# makeToneBoard.net
KiCad netlist of a schematic drawn in EAGLE
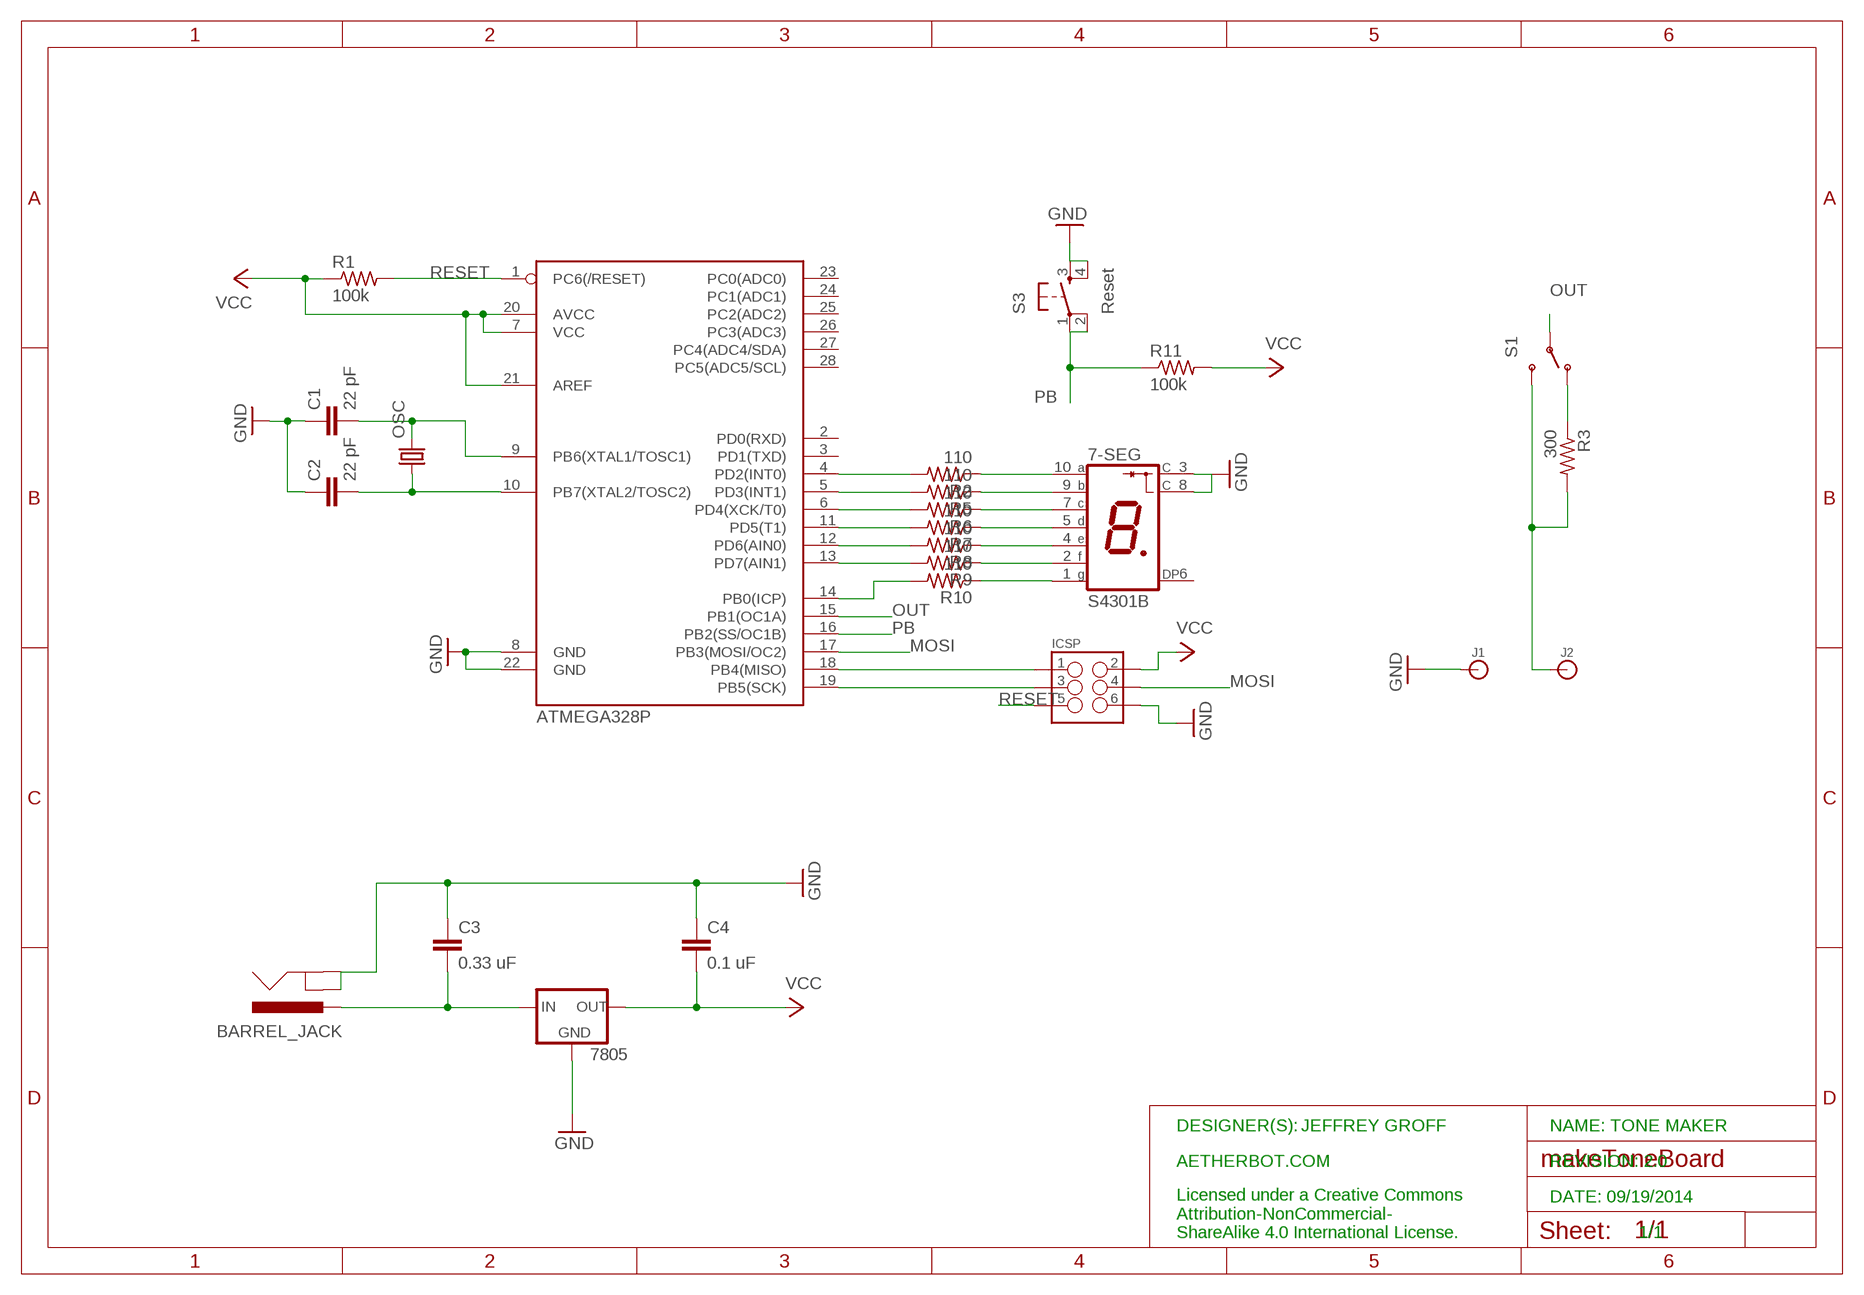
[diagram p0: schematic, sheet 1]

(export (version "E")
  (design (tool "Eeschema 10.0.6"))
  (components
    (comp (ref "7-SEG")
      (value "S4301B")
      (footprint "eagle-import:S4301B")
      (libsource (lib "eagle-import") (part "S4301B"))
    )
    (comp (ref "7805")
      (value "V_REG_78XXSINK")
      (footprint "eagle-import:TO220-IGO")
      (libsource (lib "eagle-import") (part "V_REG_78XXSINK"))
    )
    (comp (ref "BARREL_JACK")
      (value "POWER_JACKPTH")
      (footprint "eagle-import:POWER_JACK_PTH")
      (libsource (lib "eagle-import") (part "POWER_JACKPTH"))
    )
    (comp (ref "C1")
      (value "22 pF")
      (footprint "eagle-import:CAP-PTH-SMALL-KIT")
      (libsource (lib "eagle-import") (part "CAPKIT"))
    )
    (comp (ref "C2")
      (value "22 pF")
      (footprint "eagle-import:CAP-PTH-SMALL-KIT")
      (libsource (lib "eagle-import") (part "CAPKIT"))
    )
    (comp (ref "C3")
      (value "0.33 uF")
      (footprint "eagle-import:CAP-PTH-SMALLEZ")
      (libsource (lib "eagle-import") (part "CAPEZ"))
    )
    (comp (ref "C4")
      (value "0.1 uF")
      (footprint "eagle-import:CAP-PTH-SMALLEZ")
      (libsource (lib "eagle-import") (part "CAPEZ"))
    )
    (comp (ref "ICSP")
      (value "M03X2NO_SILK")
      (footprint "eagle-import:2X3-NS")
      (libsource (lib "eagle-import") (part "M03X2NO_SILK"))
    )
    (comp (ref "J1")
      (value "BANANA_CONN")
      (footprint "eagle-import:BANANA_CONN")
      (libsource (lib "eagle-import") (part "BANANA_CONN"))
    )
    (comp (ref "J2")
      (value "BANANA_CONN")
      (footprint "eagle-import:BANANA_CONN")
      (libsource (lib "eagle-import") (part "BANANA_CONN"))
    )
    (comp (ref "OSC")
      (value "CRYSTALHC49S")
      (footprint "eagle-import:HC49_S")
      (libsource (lib "eagle-import") (part "CRYSTALHC49S"))
    )
    (comp (ref "R1")
      (value "100k")
      (footprint "eagle-import:0204_7")
      (libsource (lib "eagle-import") (part "R-US_0204/7"))
    )
    (comp (ref "R2")
      (value "110")
      (footprint "eagle-import:0204_7")
      (libsource (lib "eagle-import") (part "R-US_0204/7"))
    )
    (comp (ref "R3")
      (value "300")
      (footprint "eagle-import:0204_7")
      (libsource (lib "eagle-import") (part "R-US_0204/7"))
    )
    (comp (ref "R5")
      (value "110")
      (footprint "eagle-import:0204_7")
      (libsource (lib "eagle-import") (part "R-US_0204/7"))
    )
    (comp (ref "R6")
      (value "110")
      (footprint "eagle-import:0204_7")
      (libsource (lib "eagle-import") (part "R-US_0204/7"))
    )
    (comp (ref "R7")
      (value "110")
      (footprint "eagle-import:0204_7")
      (libsource (lib "eagle-import") (part "R-US_0204/7"))
    )
    (comp (ref "R8")
      (value "110")
      (footprint "eagle-import:0204_7")
      (libsource (lib "eagle-import") (part "R-US_0204/7"))
    )
    (comp (ref "R9")
      (value "110")
      (footprint "eagle-import:0204_7")
      (libsource (lib "eagle-import") (part "R-US_0204/7"))
    )
    (comp (ref "R10")
      (value "110")
      (footprint "eagle-import:0204_7")
      (libsource (lib "eagle-import") (part "R-US_0204/7"))
    )
    (comp (ref "R11")
      (value "100k")
      (footprint "eagle-import:0204_7")
      (libsource (lib "eagle-import") (part "R-US_0204/7"))
    )
    (comp (ref "S1")
      (value "LED PWR")
      (footprint "eagle-import:SWITCH-SPDT")
      (libsource (lib "eagle-import") (part "SWITCH-SPDTPTH"))
    )
    (comp (ref "S3")
      (value "Reset")
      (footprint "eagle-import:TACTILE-PTH")
      (libsource (lib "eagle-import") (part "TAC_SWITCHPTH"))
    )
    (comp (ref "U1")
      (value "ATMEGA328P")
      (footprint "eagle-import:DIL28-3")
      (libsource (lib "eagle-import") (part "ATMEGA328P_PDIP"))
    )
  )
  (nets
    (net (code "1") (name "/MOSI") (class "Default")
      (node (ref "ICSP") (pin "4") (pinfunction "4_4") (pintype "bidirectional"))
      (node (ref "U1") (pin "17") (pinfunction "PB3(MOSI/OC2)_17") (pintype "bidirectional"))
    )
    (net (code "2") (name "/OUT") (class "Default")
      (node (ref "S1") (pin "2") (pinfunction "P_2") (pintype "passive"))
      (node (ref "U1") (pin "15") (pinfunction "PB1(OC1A)_15") (pintype "bidirectional"))
    )
    (net (code "3") (name "/PB") (class "Default")
      (node (ref "R11") (pin "1") (pinfunction "1_1") (pintype "passive"))
      (node (ref "S3") (pin "1") (pinfunction "1_1") (pintype "passive"))
      (node (ref "S3") (pin "2") (pinfunction "2_2") (pintype "passive"))
      (node (ref "U1") (pin "16") (pinfunction "PB2(SS/OC1B)_16") (pintype "bidirectional"))
    )
    (net (code "4") (name "/RESET") (class "Default")
      (node (ref "ICSP") (pin "5") (pinfunction "5_5") (pintype "bidirectional"))
      (node (ref "R1") (pin "2") (pinfunction "2_2") (pintype "passive"))
      (node (ref "U1") (pin "1") (pinfunction "PC6(/RESET)_1") (pintype "bidirectional"))
    )
    (net (code "5") (name "GND") (class "Default")
      (node (ref "7-SEG") (pin "3") (pinfunction "C_3") (pintype "passive"))
      (node (ref "7-SEG") (pin "8") (pinfunction "C_8") (pintype "passive"))
      (node (ref "7805") (pin "GND") (pinfunction "GND_GND") (pintype "input"))
      (node (ref "BARREL_JACK") (pin "GND") (pinfunction "GND_GND") (pintype "bidirectional"))
      (node (ref "BARREL_JACK") (pin "GNDBREAK") (pinfunction "GNDBREAK_GNDBREAK") (pintype "bidirectional"))
      (node (ref "C1") (pin "1") (pinfunction "1_1") (pintype "passive"))
      (node (ref "C2") (pin "1") (pinfunction "1_1") (pintype "passive"))
      (node (ref "C3") (pin "1") (pinfunction "1_1") (pintype "passive"))
      (node (ref "C4") (pin "1") (pinfunction "1_1") (pintype "passive"))
      (node (ref "ICSP") (pin "6") (pinfunction "6_6") (pintype "bidirectional"))
      (node (ref "J1") (pin "P$1") (pinfunction "1_P$1") (pintype "passive"))
      (node (ref "S3") (pin "3") (pinfunction "3_3") (pintype "passive"))
      (node (ref "S3") (pin "4") (pinfunction "4_4") (pintype "passive"))
      (node (ref "U1") (pin "22") (pinfunction "GND_22") (pintype "bidirectional"))
      (node (ref "U1") (pin "8") (pinfunction "GND_8") (pintype "bidirectional"))
    )
    (net (code "6") (name "Net-(7-SEG-A)") (class "Default")
      (node (ref "7-SEG") (pin "10") (pinfunction "A_10") (pintype "passive"))
      (node (ref "R2") (pin "1") (pinfunction "1_1") (pintype "passive"))
    )
    (net (code "7") (name "Net-(7-SEG-B)") (class "Default")
      (node (ref "7-SEG") (pin "9") (pinfunction "B_9") (pintype "passive"))
      (node (ref "R5") (pin "1") (pinfunction "1_1") (pintype "passive"))
    )
    (net (code "8") (name "Net-(7-SEG-C-Pad7)") (class "Default")
      (node (ref "7-SEG") (pin "7") (pinfunction "C_7") (pintype "passive"))
      (node (ref "R6") (pin "1") (pinfunction "1_1") (pintype "passive"))
    )
    (net (code "9") (name "Net-(7-SEG-D)") (class "Default")
      (node (ref "7-SEG") (pin "5") (pinfunction "D_5") (pintype "passive"))
      (node (ref "R7") (pin "1") (pinfunction "1_1") (pintype "passive"))
    )
    (net (code "10") (name "Net-(7-SEG-E)") (class "Default")
      (node (ref "7-SEG") (pin "4") (pinfunction "E_4") (pintype "passive"))
      (node (ref "R8") (pin "1") (pinfunction "1_1") (pintype "passive"))
    )
    (net (code "11") (name "Net-(7-SEG-F)") (class "Default")
      (node (ref "7-SEG") (pin "2") (pinfunction "F_2") (pintype "passive"))
      (node (ref "R9") (pin "1") (pinfunction "1_1") (pintype "passive"))
    )
    (net (code "12") (name "Net-(7-SEG-G)") (class "Default")
      (node (ref "7-SEG") (pin "1") (pinfunction "G_1") (pintype "passive"))
      (node (ref "R10") (pin "1") (pinfunction "1_1") (pintype "passive"))
    )
    (net (code "13") (name "Net-(7805-PadIN)") (class "Default")
      (node (ref "7805") (pin "IN") (pinfunction "IN_IN") (pintype "input"))
      (node (ref "BARREL_JACK") (pin "PWR") (pinfunction "PWR_PWR") (pintype "bidirectional"))
      (node (ref "C3") (pin "2") (pinfunction "2_2") (pintype "passive"))
    )
    (net (code "14") (name "Net-(J2-1)") (class "Default")
      (node (ref "J2") (pin "P$1") (pinfunction "1_P$1") (pintype "passive"))
      (node (ref "R3") (pin "2") (pinfunction "2_2") (pintype "passive"))
      (node (ref "S1") (pin "3") (pinfunction "S_3") (pintype "passive"))
    )
    (net (code "15") (name "Net-(S1-O)") (class "Default")
      (node (ref "R3") (pin "1") (pinfunction "1_1") (pintype "passive"))
      (node (ref "S1") (pin "1") (pinfunction "O_1") (pintype "passive"))
    )
    (net (code "16") (name "Net-(U1-PB0(ICP))") (class "Default")
      (node (ref "R10") (pin "2") (pinfunction "2_2") (pintype "passive"))
      (node (ref "U1") (pin "14") (pinfunction "PB0(ICP)_14") (pintype "bidirectional"))
    )
    (net (code "17") (name "Net-(U1-PB4(MISO))") (class "Default")
      (node (ref "ICSP") (pin "1") (pinfunction "1_1") (pintype "bidirectional"))
      (node (ref "U1") (pin "18") (pinfunction "PB4(MISO)_18") (pintype "bidirectional"))
    )
    (net (code "18") (name "Net-(U1-PB5(SCK))") (class "Default")
      (node (ref "ICSP") (pin "3") (pinfunction "3_3") (pintype "bidirectional"))
      (node (ref "U1") (pin "19") (pinfunction "PB5(SCK)_19") (pintype "bidirectional"))
    )
    (net (code "19") (name "Net-(U1-PB6(XTAL1{slash}TOSC1))") (class "Default")
      (node (ref "C1") (pin "2") (pinfunction "2_2") (pintype "passive"))
      (node (ref "OSC") (pin "2") (pinfunction "2_2") (pintype "passive"))
      (node (ref "U1") (pin "9") (pinfunction "PB6(XTAL1/TOSC1)_9") (pintype "bidirectional"))
    )
    (net (code "20") (name "Net-(U1-PB7(XTAL2{slash}TOSC2))") (class "Default")
      (node (ref "C2") (pin "2") (pinfunction "2_2") (pintype "passive"))
      (node (ref "OSC") (pin "1") (pinfunction "1_1") (pintype "passive"))
      (node (ref "U1") (pin "10") (pinfunction "PB7(XTAL2/TOSC2)_10") (pintype "bidirectional"))
    )
    (net (code "21") (name "Net-(U1-PD2(INT0))") (class "Default")
      (node (ref "R2") (pin "2") (pinfunction "2_2") (pintype "passive"))
      (node (ref "U1") (pin "4") (pinfunction "PD2(INT0)_4") (pintype "bidirectional"))
    )
    (net (code "22") (name "Net-(U1-PD3(INT1))") (class "Default")
      (node (ref "R5") (pin "2") (pinfunction "2_2") (pintype "passive"))
      (node (ref "U1") (pin "5") (pinfunction "PD3(INT1)_5") (pintype "bidirectional"))
    )
    (net (code "23") (name "Net-(U1-PD4(XCK{slash}T0))") (class "Default")
      (node (ref "R6") (pin "2") (pinfunction "2_2") (pintype "passive"))
      (node (ref "U1") (pin "6") (pinfunction "PD4(XCK/T0)_6") (pintype "bidirectional"))
    )
    (net (code "24") (name "Net-(U1-PD5(T1))") (class "Default")
      (node (ref "R7") (pin "2") (pinfunction "2_2") (pintype "passive"))
      (node (ref "U1") (pin "11") (pinfunction "PD5(T1)_11") (pintype "bidirectional"))
    )
    (net (code "25") (name "Net-(U1-PD6(AIN0))") (class "Default")
      (node (ref "R8") (pin "2") (pinfunction "2_2") (pintype "passive"))
      (node (ref "U1") (pin "12") (pinfunction "PD6(AIN0)_12") (pintype "bidirectional"))
    )
    (net (code "26") (name "Net-(U1-PD7(AIN1))") (class "Default")
      (node (ref "R9") (pin "2") (pinfunction "2_2") (pintype "passive"))
      (node (ref "U1") (pin "13") (pinfunction "PD7(AIN1)_13") (pintype "bidirectional"))
    )
    (net (code "27") (name "VCC") (class "Default")
      (node (ref "7805") (pin "OUT") (pinfunction "OUT_OUT") (pintype "output"))
      (node (ref "C4") (pin "2") (pinfunction "2_2") (pintype "passive"))
      (node (ref "ICSP") (pin "2") (pinfunction "2_2") (pintype "bidirectional"))
      (node (ref "R1") (pin "1") (pinfunction "1_1") (pintype "passive"))
      (node (ref "R11") (pin "2") (pinfunction "2_2") (pintype "passive"))
      (node (ref "U1") (pin "20") (pinfunction "AVCC_20") (pintype "bidirectional"))
      (node (ref "U1") (pin "21") (pinfunction "AREF_21") (pintype "bidirectional"))
      (node (ref "U1") (pin "7") (pinfunction "VCC_7") (pintype "bidirectional"))
    )
    (net (code "28") (name "unconnected-(7-SEG-DP-Pad6)") (class "Default")
      (node (ref "7-SEG") (pin "6") (pinfunction "DP_6") (pintype "passive"))
    )
    (net (code "29") (name "unconnected-(U1-PC0(ADC0)-Pad23)") (class "Default")
      (node (ref "U1") (pin "23") (pinfunction "PC0(ADC0)_23") (pintype "bidirectional"))
    )
    (net (code "30") (name "unconnected-(U1-PC1(ADC1)-Pad24)") (class "Default")
      (node (ref "U1") (pin "24") (pinfunction "PC1(ADC1)_24") (pintype "bidirectional"))
    )
    (net (code "31") (name "unconnected-(U1-PC2(ADC2)-Pad25)") (class "Default")
      (node (ref "U1") (pin "25") (pinfunction "PC2(ADC2)_25") (pintype "bidirectional"))
    )
    (net (code "32") (name "unconnected-(U1-PC3(ADC3)-Pad26)") (class "Default")
      (node (ref "U1") (pin "26") (pinfunction "PC3(ADC3)_26") (pintype "bidirectional"))
    )
    (net (code "33") (name "unconnected-(U1-PC4(ADC4{slash}SDA)-Pad27)") (class "Default")
      (node (ref "U1") (pin "27") (pinfunction "PC4(ADC4/SDA)_27") (pintype "bidirectional"))
    )
    (net (code "34") (name "unconnected-(U1-PC5(ADC5{slash}SCL)-Pad28)") (class "Default")
      (node (ref "U1") (pin "28") (pinfunction "PC5(ADC5/SCL)_28") (pintype "bidirectional"))
    )
    (net (code "35") (name "unconnected-(U1-PD0(RXD)-Pad2)") (class "Default")
      (node (ref "U1") (pin "2") (pinfunction "PD0(RXD)_2") (pintype "bidirectional"))
    )
    (net (code "36") (name "unconnected-(U1-PD1(TXD)-Pad3)") (class "Default")
      (node (ref "U1") (pin "3") (pinfunction "PD1(TXD)_3") (pintype "bidirectional"))
    )
  )
)
